# SSR.net
KiCad netlist of a schematic drawn in Altium Designer
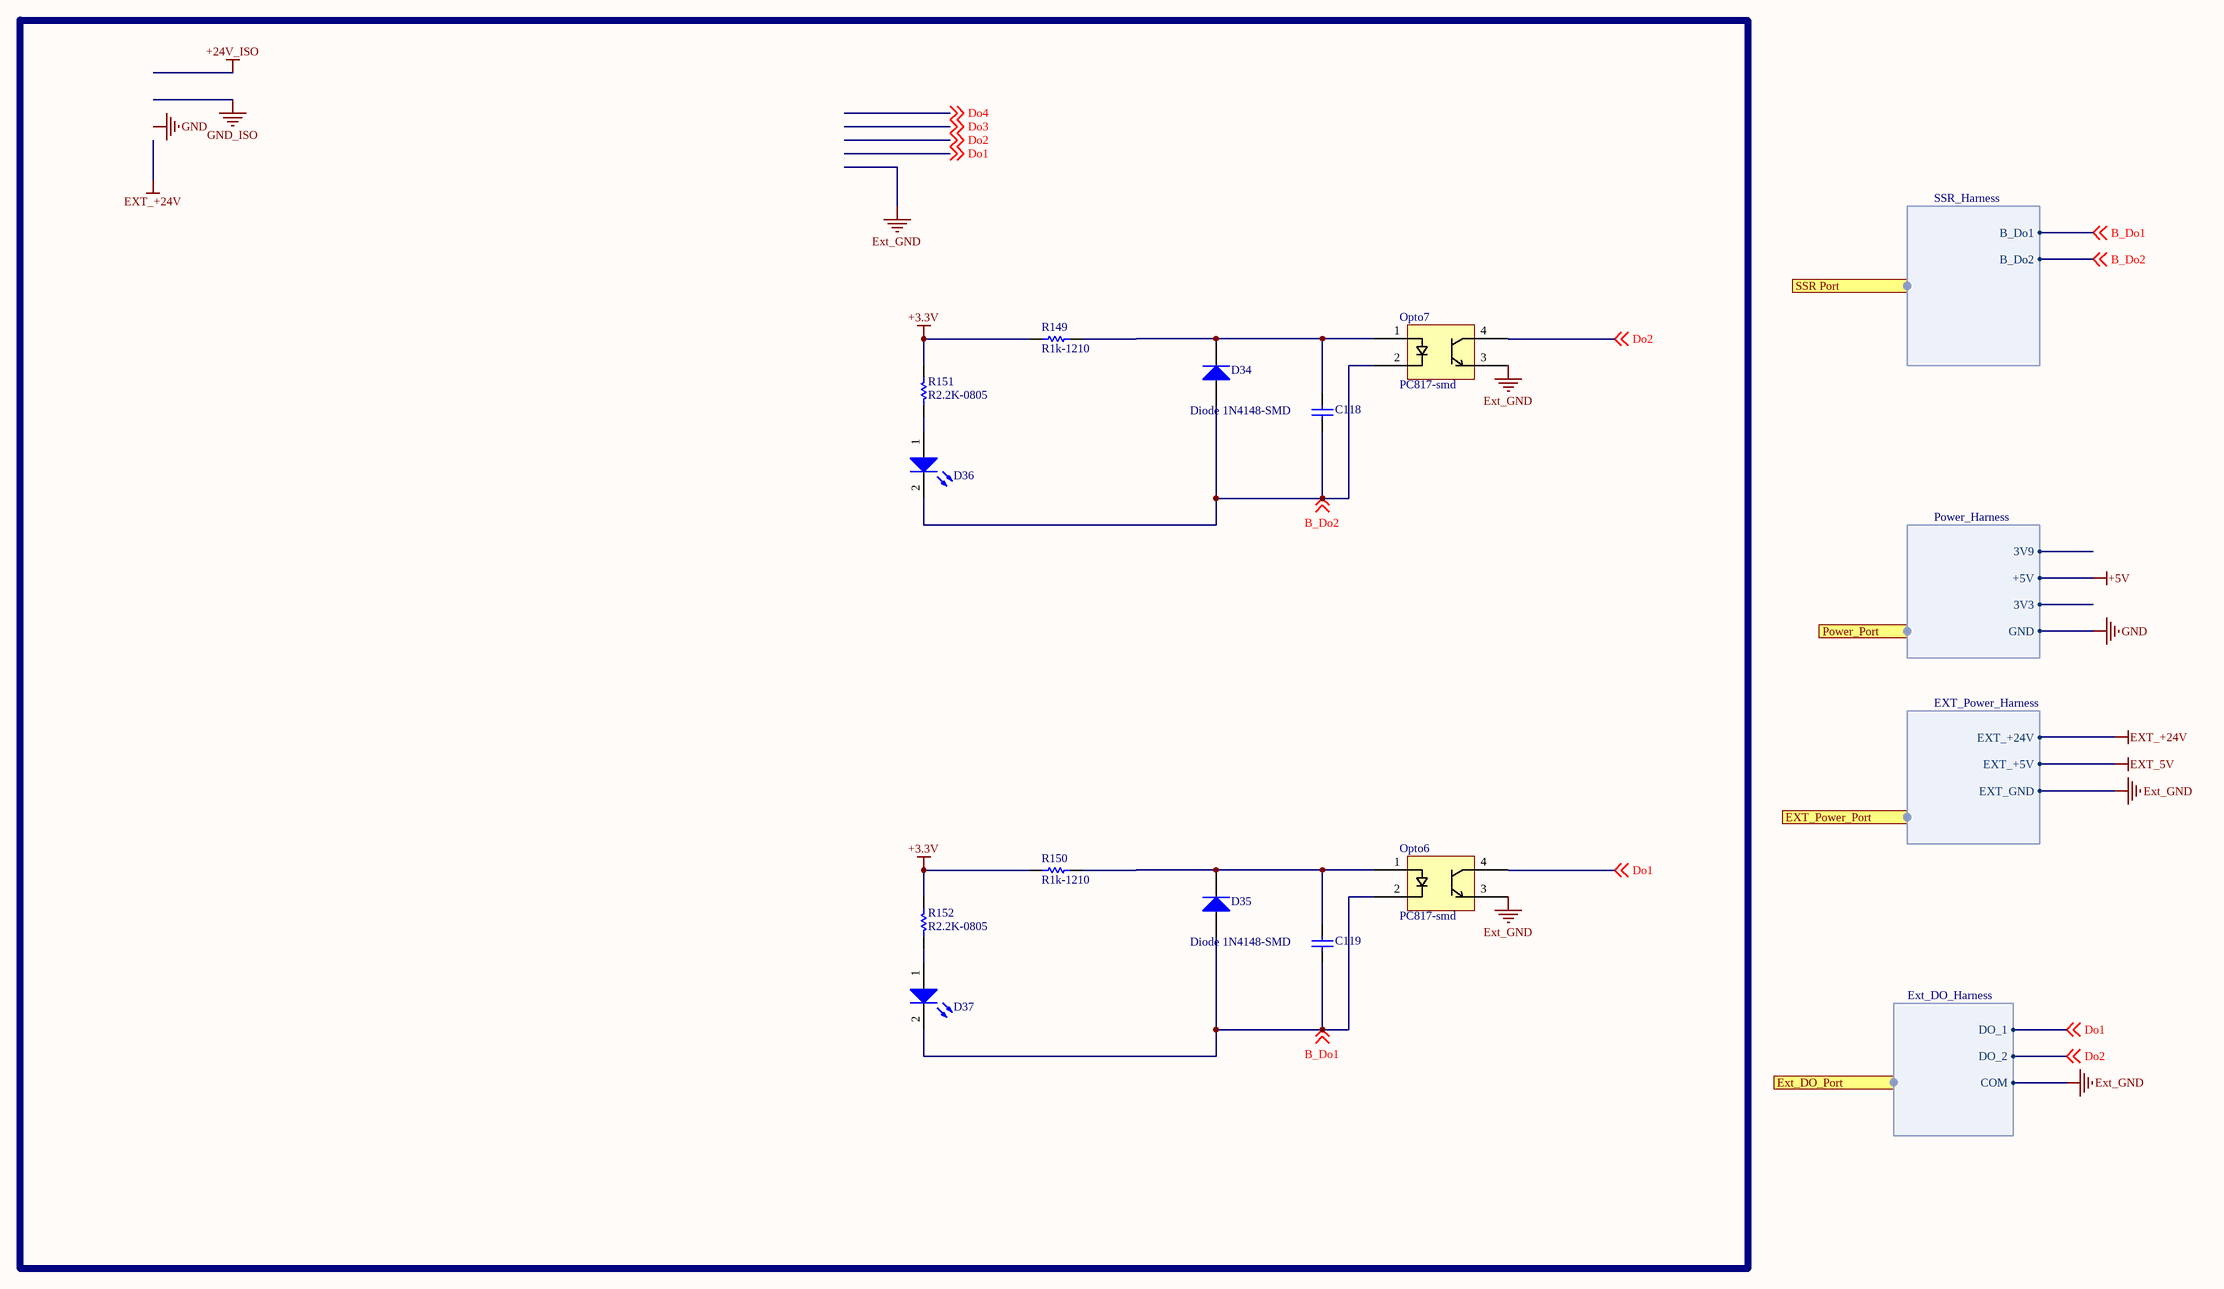
[diagram p0: SSR.SchDoc]

(export (version "E")
  (design (tool "Eeschema 10.0.6"))
  (components
    (comp (ref "C118")
      (value "~")
      (footprint "CRF06031")
      (description "Capacitor")
      (fields (field (name "DIGI-KEY_PART_NUMBER") "490-4789-1-ND"))
      (libsource (lib "Miscellaneous Devices") (part "Cap"))
    )
    (comp (ref "C119")
      (value "~")
      (footprint "CRF06031")
      (description "Capacitor")
      (fields (field (name "DIGI-KEY_PART_NUMBER") "490-4789-1-ND"))
      (libsource (lib "Miscellaneous Devices") (part "Cap"))
    )
    (comp (ref "D34")
      (value "Diode 1N4148-SMD")
      (footprint "d1206")
      (description "1 Amp Fast Recovery Rectifier")
      (fields (field (name "DIGI-KEY_PART_NUMBER") "1N4148WSFSTR-ND"))
      (libsource (lib "Miscellaneous Devices") (part "Diode 1N4934"))
    )
    (comp (ref "D35")
      (value "Diode 1N4148-SMD")
      (footprint "d1206")
      (description "1 Amp Fast Recovery Rectifier")
      (fields (field (name "DIGI-KEY_PART_NUMBER") "1N4148WSFSTR-ND"))
      (libsource (lib "Miscellaneous Devices") (part "Diode 1N4934"))
    )
    (comp (ref "D36")
      (value "LED_0805_green")
      (footprint "0805-LED")
      (libsource (lib "HosseinLib") (part "LED_0805"))
    )
    (comp (ref "D37")
      (value "LED_0805_green")
      (footprint "0805-LED")
      (libsource (lib "HosseinLib") (part "LED_0805"))
    )
    (comp (ref "Opto6")
      (value "PC817-smd")
      (footprint "PC817_SMD1")
      (fields (field (name "DIGI-KEY_PART_NUMBER") "2007-APC-817D1-SLTR-ND"))
      (libsource (lib "Almas Co") (part "PC817"))
    )
    (comp (ref "Opto7")
      (value "PC817-smd")
      (footprint "PC817_SMD1")
      (fields (field (name "DIGI-KEY_PART_NUMBER") "2007-APC-817D1-SLTR-ND"))
      (libsource (lib "Almas Co") (part "PC817"))
    )
    (comp (ref "R149")
      (value "R1k-1210")
      (footprint "r1210")
      (description "Resistor")
      (fields (field (name "DIGI-KEY_PART_NUMBER") "YAG2296TR-ND"))
      (libsource (lib "Miscellaneous Devices") (part "Res1"))
    )
    (comp (ref "R150")
      (value "R1k-1210")
      (footprint "r1210")
      (description "Resistor")
      (fields (field (name "DIGI-KEY_PART_NUMBER") "YAG2296TR-ND"))
      (libsource (lib "Miscellaneous Devices") (part "Res1"))
    )
    (comp (ref "R151")
      (value "R2.2K-0805")
      (footprint "CRF06031")
      (description "Resistor")
      (fields (field (name "DIGI-KEY_PART_NUMBER") "311-2.20KCRTR-ND"))
      (libsource (lib "Miscellaneous Devices") (part "Res1"))
    )
    (comp (ref "R152")
      (value "R2.2K-0805")
      (footprint "CRF06031")
      (description "Resistor")
      (fields (field (name "DIGI-KEY_PART_NUMBER") "311-2.20KCRTR-ND"))
      (libsource (lib "Miscellaneous Devices") (part "Res1"))
    )
  )
  (nets
    (net (code "5") (name "+3.3V") (class "Default")
      (node (ref "R149") (pin "1") (pinfunction "1_1") (pintype "passive"))
      (node (ref "R150") (pin "1") (pinfunction "1_1") (pintype "passive"))
      (node (ref "R151") (pin "2") (pinfunction "2_2") (pintype "passive"))
      (node (ref "R152") (pin "2") (pinfunction "2_2") (pintype "passive"))
    )
    (net (code "12") (name "B_Do1") (class "Default")
      (node (ref "C119") (pin "1") (pinfunction "1_1") (pintype "passive"))
      (node (ref "D35") (pin "1") (pinfunction "A_1") (pintype "passive"))
      (node (ref "D37") (pin "2") (pinfunction "K_2") (pintype "passive"))
      (node (ref "Opto6") (pin "2") (pintype "passive"))
    )
    (net (code "13") (name "B_Do2") (class "Default")
      (node (ref "C118") (pin "1") (pinfunction "1_1") (pintype "passive"))
      (node (ref "D34") (pin "1") (pinfunction "A_1") (pintype "passive"))
      (node (ref "D36") (pin "2") (pinfunction "K_2") (pintype "passive"))
      (node (ref "Opto7") (pin "2") (pintype "passive"))
    )
    (net (code "14") (name "Do1") (class "Default") (node (ref "Opto6") (pin "4") (pintype "passive")))
    (net (code "15") (name "Do2") (class "Default") (node (ref "Opto7") (pin "4") (pintype "passive")))
    (net (code "20") (name "Ext_GND") (class "Default")
      (node (ref "Opto6") (pin "3") (pintype "passive"))
      (node (ref "Opto7") (pin "3") (pintype "passive"))
    )
    (net (code "23") (name "Net-(D34-K)") (class "Default")
      (node (ref "C118") (pin "2") (pinfunction "2_2") (pintype "passive"))
      (node (ref "D34") (pin "2") (pinfunction "K_2") (pintype "passive"))
      (node (ref "Opto7") (pin "1") (pintype "passive"))
      (node (ref "R149") (pin "2") (pinfunction "2_2") (pintype "passive"))
    )
    (net (code "24") (name "Net-(D35-K)") (class "Default")
      (node (ref "C119") (pin "2") (pinfunction "2_2") (pintype "passive"))
      (node (ref "D35") (pin "2") (pinfunction "K_2") (pintype "passive"))
      (node (ref "Opto6") (pin "1") (pintype "passive"))
      (node (ref "R150") (pin "2") (pinfunction "2_2") (pintype "passive"))
    )
    (net (code "25") (name "Net-(D36-A)") (class "Default")
      (node (ref "D36") (pin "1") (pinfunction "A_1") (pintype "passive"))
      (node (ref "R151") (pin "1") (pinfunction "1_1") (pintype "passive"))
    )
    (net (code "26") (name "Net-(D37-A)") (class "Default")
      (node (ref "D37") (pin "1") (pinfunction "A_1") (pintype "passive"))
      (node (ref "R152") (pin "1") (pinfunction "1_1") (pintype "passive"))
    )
  )
)
